# stm8l101_core.net
KiCad netlist of a schematic drawn in EAGLE
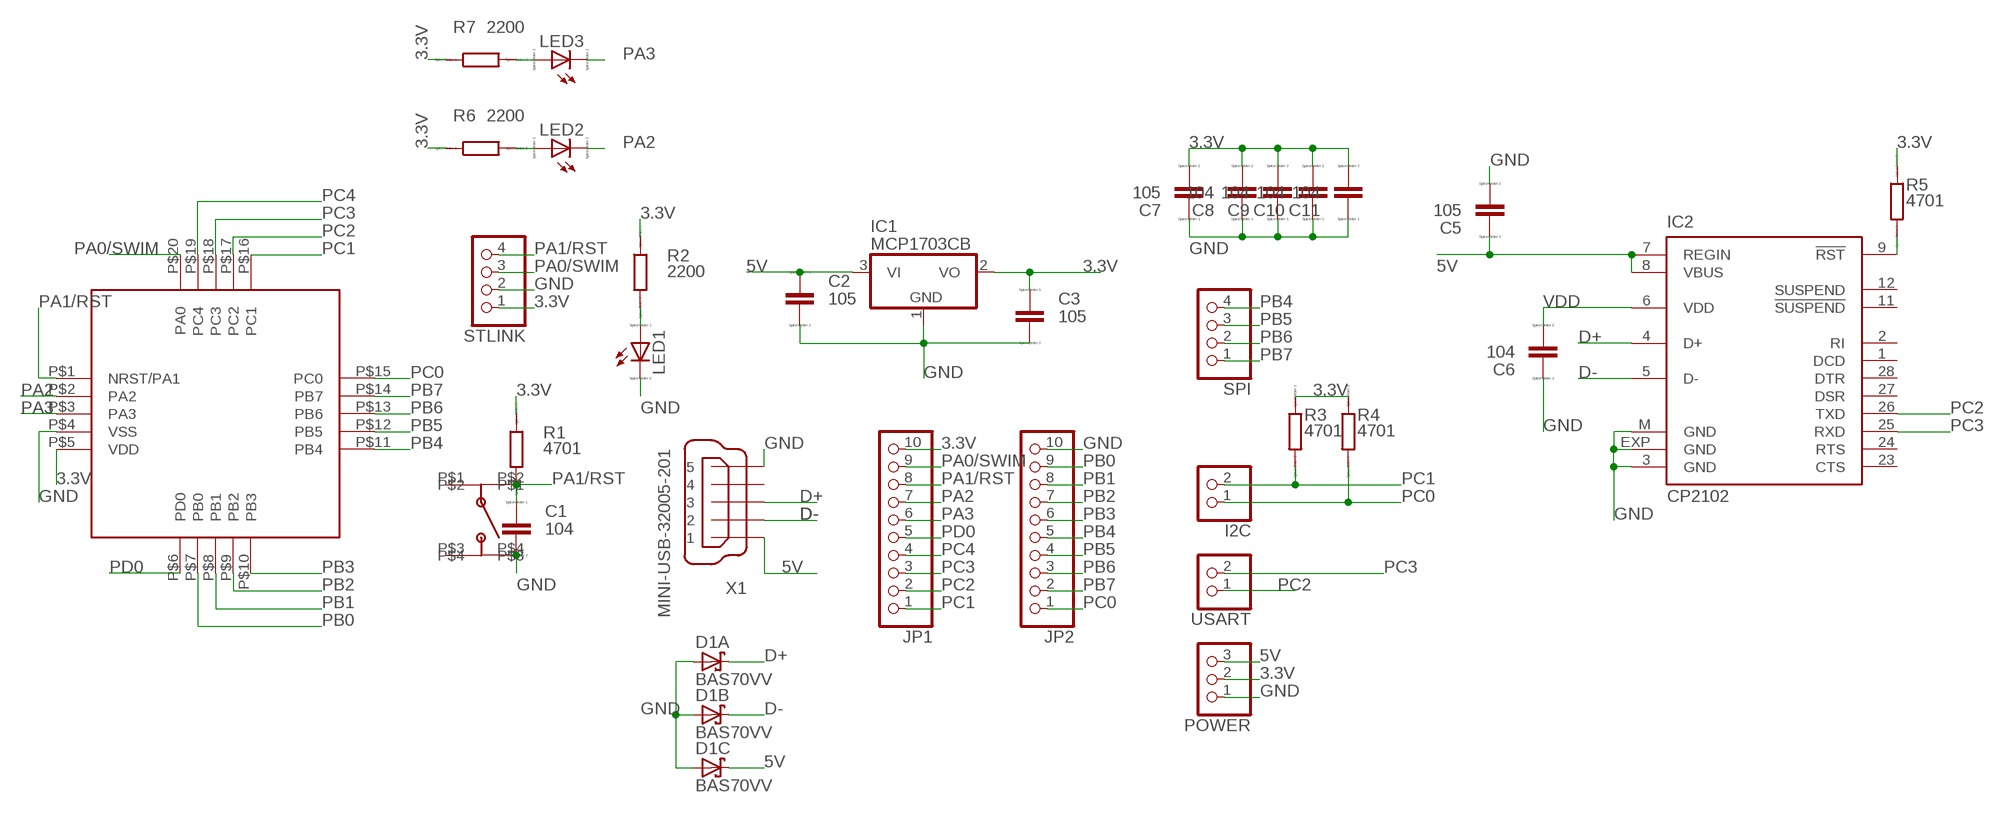
[diagram p0: schematic, sheet 1]

(export (version "E")
  (design (tool "Eeschema 10.0.6"))
  (components
    (comp (ref "C1")
      (value "104")
      (footprint "eagle-import:C0603")
      (libsource (lib "eagle-import") (part "CC0603"))
    )
    (comp (ref "C2")
      (value "105")
      (footprint "eagle-import:C0603")
      (libsource (lib "eagle-import") (part "CC0603"))
    )
    (comp (ref "C3")
      (value "105")
      (footprint "eagle-import:C0603")
      (libsource (lib "eagle-import") (part "CC0603"))
    )
    (comp (ref "C5")
      (value "105")
      (footprint "eagle-import:C0603")
      (libsource (lib "eagle-import") (part "CC0603"))
    )
    (comp (ref "C6")
      (value "104")
      (footprint "eagle-import:C0603")
      (libsource (lib "eagle-import") (part "CC0603"))
    )
    (comp (ref "C7")
      (value "105")
      (footprint "eagle-import:C0603")
      (libsource (lib "eagle-import") (part "CC0603"))
    )
    (comp (ref "C8")
      (value "104")
      (footprint "eagle-import:C0603")
      (libsource (lib "eagle-import") (part "CC0603"))
    )
    (comp (ref "C9")
      (value "104")
      (footprint "eagle-import:C0603")
      (libsource (lib "eagle-import") (part "CC0603"))
    )
    (comp (ref "C10")
      (value "104")
      (footprint "eagle-import:C0603")
      (libsource (lib "eagle-import") (part "CC0603"))
    )
    (comp (ref "C11")
      (value "104")
      (footprint "eagle-import:C0603")
      (libsource (lib "eagle-import") (part "CC0603"))
    )
    (comp (ref "D1")
      (value "BAS70VV")
      (footprint "eagle-import:SOT666")
      (libsource (lib "eagle-import") (part "BAS70VV"))
    )
    (comp (ref "I2C")
      (value "PINHD-1X2")
      (footprint "eagle-import:1X02")
      (libsource (lib "eagle-import") (part "PINHD-1X2"))
    )
    (comp (ref "IC1")
      (value "MCP1703CB")
      (footprint "eagle-import:SOT23")
      (libsource (lib "eagle-import") (part "MCP1703CB"))
    )
    (comp (ref "IC2")
      (value "CP2102")
      (footprint "eagle-import:MLP28")
      (fields (field (name "MF") "FARNELL") (field (name "MPN") "CP2102-GM"))
      (libsource (lib "eagle-import") (part "CP2102"))
    )
    (comp (ref "JP1")
      (value "PINHD-1X10")
      (footprint "eagle-import:1X10")
      (libsource (lib "eagle-import") (part "PINHD-1X10"))
    )
    (comp (ref "JP2")
      (value "PINHD-1X10")
      (footprint "eagle-import:1X10")
      (libsource (lib "eagle-import") (part "PINHD-1X10"))
    )
    (comp (ref "LED1")
      (value "LED_ESML0603")
      (footprint "eagle-import:LED_SML0603")
      (libsource (lib "eagle-import") (part "LED_ESML0603"))
    )
    (comp (ref "LED2")
      (value "LED_ESML0603")
      (footprint "eagle-import:LED_SML0603")
      (libsource (lib "eagle-import") (part "LED_ESML0603"))
    )
    (comp (ref "LED3")
      (value "LED_ESML0603")
      (footprint "eagle-import:LED_SML0603")
      (libsource (lib "eagle-import") (part "LED_ESML0603"))
    )
    (comp (ref "POWER")
      (value "PINHD-1X3")
      (footprint "eagle-import:1X03")
      (libsource (lib "eagle-import") (part "PINHD-1X3"))
    )
    (comp (ref "R1")
      (value "4701")
      (footprint "eagle-import:R0603")
      (libsource (lib "eagle-import") (part "RR0603"))
    )
    (comp (ref "R2")
      (value "2200")
      (footprint "eagle-import:R0603")
      (libsource (lib "eagle-import") (part "RR0603"))
    )
    (comp (ref "R3")
      (value "4701")
      (footprint "eagle-import:R0603")
      (libsource (lib "eagle-import") (part "RR0603"))
    )
    (comp (ref "R4")
      (value "4701")
      (footprint "eagle-import:R0603")
      (libsource (lib "eagle-import") (part "RR0603"))
    )
    (comp (ref "R5")
      (value "4701")
      (footprint "eagle-import:R0603")
      (libsource (lib "eagle-import") (part "RR0603"))
    )
    (comp (ref "R6")
      (value "2200")
      (footprint "eagle-import:R0603")
      (libsource (lib "eagle-import") (part "RR0603"))
    )
    (comp (ref "R7")
      (value "2200")
      (footprint "eagle-import:R0603")
      (libsource (lib "eagle-import") (part "RR0603"))
    )
    (comp (ref "SPI")
      (value "PINHD-1X4")
      (footprint "eagle-import:1X04")
      (libsource (lib "eagle-import") (part "PINHD-1X4"))
    )
    (comp (ref "STLINK")
      (value "PINHD-1X4")
      (footprint "eagle-import:1X04")
      (libsource (lib "eagle-import") (part "PINHD-1X4"))
    )
    (comp (ref "U$1")
      (value "STM8L101")
      (footprint "eagle-import:UFQFPN20")
      (libsource (lib "eagle-import") (part "STM8L101"))
    )
    (comp (ref "U$2")
      (value "KFC-A05")
      (footprint "eagle-import:SWITCH-4X4")
      (libsource (lib "eagle-import") (part "KFC-A05"))
    )
    (comp (ref "USART")
      (value "PINHD-1X2")
      (footprint "eagle-import:1X02")
      (libsource (lib "eagle-import") (part "PINHD-1X2"))
    )
    (comp (ref "X1")
      (value "MINI-USB-32005-201")
      (footprint "eagle-import:32005-201")
      (libsource (lib "eagle-import") (part "MINI-USB-32005-201"))
    )
  )
  (nets
    (net (code "1") (name "/3.3V") (class "Default")
      (node (ref "C10") (pin "2") (pinfunction "2_2") (pintype "passive"))
      (node (ref "C11") (pin "2") (pinfunction "2_2") (pintype "passive"))
      (node (ref "C3") (pin "1") (pinfunction "1_1") (pintype "passive"))
      (node (ref "C7") (pin "2") (pinfunction "2_2") (pintype "passive"))
      (node (ref "C8") (pin "2") (pinfunction "2_2") (pintype "passive"))
      (node (ref "C9") (pin "2") (pinfunction "2_2") (pintype "passive"))
      (node (ref "IC1") (pin "2") (pinfunction "VO_2") (pintype "passive"))
      (node (ref "JP1") (pin "10") (pinfunction "10_10") (pintype "passive"))
      (node (ref "POWER") (pin "2") (pinfunction "2_2") (pintype "passive"))
      (node (ref "R1") (pin "1") (pinfunction "1_1") (pintype "passive"))
      (node (ref "R2") (pin "1") (pinfunction "1_1") (pintype "passive"))
      (node (ref "R3") (pin "1") (pinfunction "1_1") (pintype "passive"))
      (node (ref "R4") (pin "1") (pinfunction "1_1") (pintype "passive"))
      (node (ref "R5") (pin "1") (pinfunction "1_1") (pintype "passive"))
      (node (ref "R6") (pin "1") (pinfunction "1_1") (pintype "passive"))
      (node (ref "R7") (pin "1") (pinfunction "1_1") (pintype "passive"))
      (node (ref "STLINK") (pin "1") (pinfunction "1_1") (pintype "passive"))
      (node (ref "U$1") (pin "P$5") (pinfunction "VDD_P$5") (pintype "bidirectional"))
    )
    (net (code "2") (name "/5V") (class "Default")
      (node (ref "C2") (pin "1") (pinfunction "1_1") (pintype "passive"))
      (node (ref "C5") (pin "1") (pinfunction "1_1") (pintype "passive"))
      (node (ref "D1") (pin "4") (pinfunction "C_4") (pintype "passive"))
      (node (ref "IC1") (pin "3") (pinfunction "VI_3") (pintype "input"))
      (node (ref "IC2") (pin "7") (pinfunction "REGIN_7") (pintype "passive"))
      (node (ref "IC2") (pin "8") (pinfunction "VBUS_8") (pintype "input"))
      (node (ref "POWER") (pin "3") (pinfunction "3_3") (pintype "passive"))
      (node (ref "X1") (pin "1") (pinfunction "1_1") (pintype "passive"))
    )
    (net (code "3") (name "/D+") (class "Default")
      (node (ref "D1") (pin "6") (pinfunction "C_6") (pintype "passive"))
      (node (ref "IC2") (pin "4") (pinfunction "D+_4") (pintype "bidirectional"))
      (node (ref "X1") (pin "3") (pinfunction "3_3") (pintype "passive"))
    )
    (net (code "4") (name "/D-") (class "Default")
      (node (ref "D1") (pin "5") (pinfunction "C_5") (pintype "passive"))
      (node (ref "IC2") (pin "5") (pinfunction "D-_5") (pintype "bidirectional"))
      (node (ref "X1") (pin "2") (pinfunction "2_2") (pintype "passive"))
    )
    (net (code "5") (name "/GND") (class "Default")
      (node (ref "C1") (pin "2") (pinfunction "2_2") (pintype "passive"))
      (node (ref "C10") (pin "1") (pinfunction "1_1") (pintype "passive"))
      (node (ref "C11") (pin "1") (pinfunction "1_1") (pintype "passive"))
      (node (ref "C2") (pin "2") (pinfunction "2_2") (pintype "passive"))
      (node (ref "C3") (pin "2") (pinfunction "2_2") (pintype "passive"))
      (node (ref "C5") (pin "2") (pinfunction "2_2") (pintype "passive"))
      (node (ref "C6") (pin "1") (pinfunction "1_1") (pintype "passive"))
      (node (ref "C7") (pin "1") (pinfunction "1_1") (pintype "passive"))
      (node (ref "C8") (pin "1") (pinfunction "1_1") (pintype "passive"))
      (node (ref "C9") (pin "1") (pinfunction "1_1") (pintype "passive"))
      (node (ref "D1") (pin "1") (pinfunction "A_1") (pintype "passive"))
      (node (ref "D1") (pin "2") (pinfunction "A_2") (pintype "passive"))
      (node (ref "D1") (pin "3") (pinfunction "A_3") (pintype "passive"))
      (node (ref "IC1") (pin "1") (pinfunction "GND_1") (pintype "passive"))
      (node (ref "IC2") (pin "3") (pinfunction "GND_3") (pintype "power_in"))
      (node (ref "IC2") (pin "EXP") (pinfunction "GND_EXP") (pintype "power_in"))
      (node (ref "IC2") (pin "M") (pinfunction "GND_M") (pintype "power_in"))
      (node (ref "JP2") (pin "10") (pinfunction "10_10") (pintype "passive"))
      (node (ref "LED1") (pin "C") (pinfunction "C_C") (pintype "passive"))
      (node (ref "POWER") (pin "1") (pinfunction "1_1") (pintype "passive"))
      (node (ref "STLINK") (pin "2") (pinfunction "2_2") (pintype "passive"))
      (node (ref "U$1") (pin "P$4") (pinfunction "VSS_P$4") (pintype "bidirectional"))
      (node (ref "U$2") (pin "P$4") (pinfunction "P$4_P$4") (pintype "bidirectional"))
      (node (ref "X1") (pin "5") (pinfunction "5_5") (pintype "passive"))
    )
    (net (code "6") (name "/PA0{slash}SWIM") (class "Default")
      (node (ref "JP1") (pin "9") (pinfunction "9_9") (pintype "passive"))
      (node (ref "STLINK") (pin "3") (pinfunction "3_3") (pintype "passive"))
      (node (ref "U$1") (pin "P$20") (pinfunction "PA0_P$20") (pintype "bidirectional"))
    )
    (net (code "7") (name "/PA1{slash}RST") (class "Default")
      (node (ref "C1") (pin "1") (pinfunction "1_1") (pintype "passive"))
      (node (ref "JP1") (pin "8") (pinfunction "8_8") (pintype "passive"))
      (node (ref "R1") (pin "2") (pinfunction "2_2") (pintype "passive"))
      (node (ref "STLINK") (pin "4") (pinfunction "4_4") (pintype "passive"))
      (node (ref "U$1") (pin "P$1") (pinfunction "NRST/PA1_P$1") (pintype "bidirectional"))
      (node (ref "U$2") (pin "P$2") (pinfunction "P$2_P$2") (pintype "bidirectional"))
    )
    (net (code "8") (name "/PA2") (class "Default")
      (node (ref "JP1") (pin "7") (pinfunction "7_7") (pintype "passive"))
      (node (ref "LED2") (pin "C") (pinfunction "C_C") (pintype "passive"))
      (node (ref "U$1") (pin "P$2") (pinfunction "PA2_P$2") (pintype "bidirectional"))
    )
    (net (code "9") (name "/PA3") (class "Default")
      (node (ref "JP1") (pin "6") (pinfunction "6_6") (pintype "passive"))
      (node (ref "LED3") (pin "C") (pinfunction "C_C") (pintype "passive"))
      (node (ref "U$1") (pin "P$3") (pinfunction "PA3_P$3") (pintype "bidirectional"))
    )
    (net (code "10") (name "/PB0") (class "Default")
      (node (ref "JP2") (pin "9") (pinfunction "9_9") (pintype "passive"))
      (node (ref "U$1") (pin "P$7") (pinfunction "PB0_P$7") (pintype "bidirectional"))
    )
    (net (code "11") (name "/PB1") (class "Default")
      (node (ref "JP2") (pin "8") (pinfunction "8_8") (pintype "passive"))
      (node (ref "U$1") (pin "P$8") (pinfunction "PB1_P$8") (pintype "bidirectional"))
    )
    (net (code "12") (name "/PB2") (class "Default")
      (node (ref "JP2") (pin "7") (pinfunction "7_7") (pintype "passive"))
      (node (ref "U$1") (pin "P$9") (pinfunction "PB2_P$9") (pintype "bidirectional"))
    )
    (net (code "13") (name "/PB3") (class "Default")
      (node (ref "JP2") (pin "6") (pinfunction "6_6") (pintype "passive"))
      (node (ref "U$1") (pin "P$10") (pinfunction "PB3_P$10") (pintype "bidirectional"))
    )
    (net (code "14") (name "/PB4") (class "Default")
      (node (ref "JP2") (pin "5") (pinfunction "5_5") (pintype "passive"))
      (node (ref "SPI") (pin "4") (pinfunction "4_4") (pintype "passive"))
      (node (ref "U$1") (pin "P$11") (pinfunction "PB4_P$11") (pintype "bidirectional"))
    )
    (net (code "15") (name "/PB5") (class "Default")
      (node (ref "JP2") (pin "4") (pinfunction "4_4") (pintype "passive"))
      (node (ref "SPI") (pin "3") (pinfunction "3_3") (pintype "passive"))
      (node (ref "U$1") (pin "P$12") (pinfunction "PB5_P$12") (pintype "bidirectional"))
    )
    (net (code "16") (name "/PB6") (class "Default")
      (node (ref "JP2") (pin "3") (pinfunction "3_3") (pintype "passive"))
      (node (ref "SPI") (pin "2") (pinfunction "2_2") (pintype "passive"))
      (node (ref "U$1") (pin "P$13") (pinfunction "PB6_P$13") (pintype "bidirectional"))
    )
    (net (code "17") (name "/PB7") (class "Default")
      (node (ref "JP2") (pin "2") (pinfunction "2_2") (pintype "passive"))
      (node (ref "SPI") (pin "1") (pinfunction "1_1") (pintype "passive"))
      (node (ref "U$1") (pin "P$14") (pinfunction "PB7_P$14") (pintype "bidirectional"))
    )
    (net (code "18") (name "/PC0") (class "Default")
      (node (ref "I2C") (pin "1") (pinfunction "1_1") (pintype "passive"))
      (node (ref "JP2") (pin "1") (pinfunction "1_1") (pintype "passive"))
      (node (ref "R4") (pin "2") (pinfunction "2_2") (pintype "passive"))
      (node (ref "U$1") (pin "P$15") (pinfunction "PC0_P$15") (pintype "bidirectional"))
    )
    (net (code "19") (name "/PC1") (class "Default")
      (node (ref "I2C") (pin "2") (pinfunction "2_2") (pintype "passive"))
      (node (ref "JP1") (pin "1") (pinfunction "1_1") (pintype "passive"))
      (node (ref "R3") (pin "2") (pinfunction "2_2") (pintype "passive"))
      (node (ref "U$1") (pin "P$16") (pinfunction "PC1_P$16") (pintype "bidirectional"))
    )
    (net (code "20") (name "/PC2") (class "Default")
      (node (ref "IC2") (pin "26") (pinfunction "TXD_26") (pintype "output"))
      (node (ref "JP1") (pin "2") (pinfunction "2_2") (pintype "passive"))
      (node (ref "U$1") (pin "P$17") (pinfunction "PC2_P$17") (pintype "bidirectional"))
      (node (ref "USART") (pin "1") (pinfunction "1_1") (pintype "passive"))
    )
    (net (code "21") (name "/PC3") (class "Default")
      (node (ref "IC2") (pin "25") (pinfunction "RXD_25") (pintype "input"))
      (node (ref "JP1") (pin "3") (pinfunction "3_3") (pintype "passive"))
      (node (ref "U$1") (pin "P$18") (pinfunction "PC3_P$18") (pintype "bidirectional"))
      (node (ref "USART") (pin "2") (pinfunction "2_2") (pintype "passive"))
    )
    (net (code "22") (name "/PC4") (class "Default")
      (node (ref "JP1") (pin "4") (pinfunction "4_4") (pintype "passive"))
      (node (ref "U$1") (pin "P$19") (pinfunction "PC4_P$19") (pintype "bidirectional"))
    )
    (net (code "23") (name "/PD0") (class "Default")
      (node (ref "JP1") (pin "5") (pinfunction "5_5") (pintype "passive"))
      (node (ref "U$1") (pin "P$6") (pinfunction "PD0_P$6") (pintype "bidirectional"))
    )
    (net (code "24") (name "/VDD") (class "Default")
      (node (ref "C6") (pin "2") (pinfunction "2_2") (pintype "passive"))
      (node (ref "IC2") (pin "6") (pinfunction "VDD_6") (pintype "power_in"))
    )
    (net (code "25") (name "Net-(IC2-~{RST})") (class "Default")
      (node (ref "IC2") (pin "9") (pinfunction "~{RST}_9") (pintype "bidirectional"))
      (node (ref "R5") (pin "2") (pinfunction "2_2") (pintype "passive"))
    )
    (net (code "26") (name "Net-(LED1-PadA)") (class "Default")
      (node (ref "LED1") (pin "A") (pinfunction "A_A") (pintype "passive"))
      (node (ref "R2") (pin "2") (pinfunction "2_2") (pintype "passive"))
    )
    (net (code "27") (name "Net-(LED2-PadA)") (class "Default")
      (node (ref "LED2") (pin "A") (pinfunction "A_A") (pintype "passive"))
      (node (ref "R6") (pin "2") (pinfunction "2_2") (pintype "passive"))
    )
    (net (code "28") (name "Net-(LED3-PadA)") (class "Default")
      (node (ref "LED3") (pin "A") (pinfunction "A_A") (pintype "passive"))
      (node (ref "R7") (pin "2") (pinfunction "2_2") (pintype "passive"))
    )
    (net (code "29") (name "unconnected-(IC2-CTS-Pad23)") (class "Default")
      (node (ref "IC2") (pin "23") (pinfunction "CTS_23") (pintype "input"))
    )
    (net (code "30") (name "unconnected-(IC2-DCD-Pad1)") (class "Default")
      (node (ref "IC2") (pin "1") (pinfunction "DCD_1") (pintype "input"))
    )
    (net (code "31") (name "unconnected-(IC2-DSR-Pad27)") (class "Default")
      (node (ref "IC2") (pin "27") (pinfunction "DSR_27") (pintype "input"))
    )
    (net (code "32") (name "unconnected-(IC2-DTR-Pad28)") (class "Default")
      (node (ref "IC2") (pin "28") (pinfunction "DTR_28") (pintype "output"))
    )
    (net (code "33") (name "unconnected-(IC2-RI-Pad2)") (class "Default")
      (node (ref "IC2") (pin "2") (pinfunction "RI_2") (pintype "input"))
    )
    (net (code "34") (name "unconnected-(IC2-RTS-Pad24)") (class "Default")
      (node (ref "IC2") (pin "24") (pinfunction "RTS_24") (pintype "output"))
    )
    (net (code "35") (name "unconnected-(IC2-SUSPEND-Pad12)") (class "Default")
      (node (ref "IC2") (pin "12") (pinfunction "SUSPEND_12") (pintype "output"))
    )
    (net (code "36") (name "unconnected-(IC2-~{SUSPEND}-Pad11)") (class "Default")
      (node (ref "IC2") (pin "11") (pinfunction "~{SUSPEND}_11") (pintype "output"))
    )
    (net (code "37") (name "unconnected-(U$2-PadP$1)") (class "Default")
      (node (ref "U$2") (pin "P$1") (pinfunction "P$1_P$1") (pintype "bidirectional"))
    )
    (net (code "38") (name "unconnected-(U$2-PadP$3)") (class "Default")
      (node (ref "U$2") (pin "P$3") (pinfunction "P$3_P$3") (pintype "bidirectional"))
    )
    (net (code "39") (name "unconnected-(X1-Pad4)") (class "Default")
      (node (ref "X1") (pin "4") (pinfunction "4_4") (pintype "passive"))
    )
  )
)
